# Light_s_Thrill.net
KiCad netlist of a schematic drawn in EAGLE
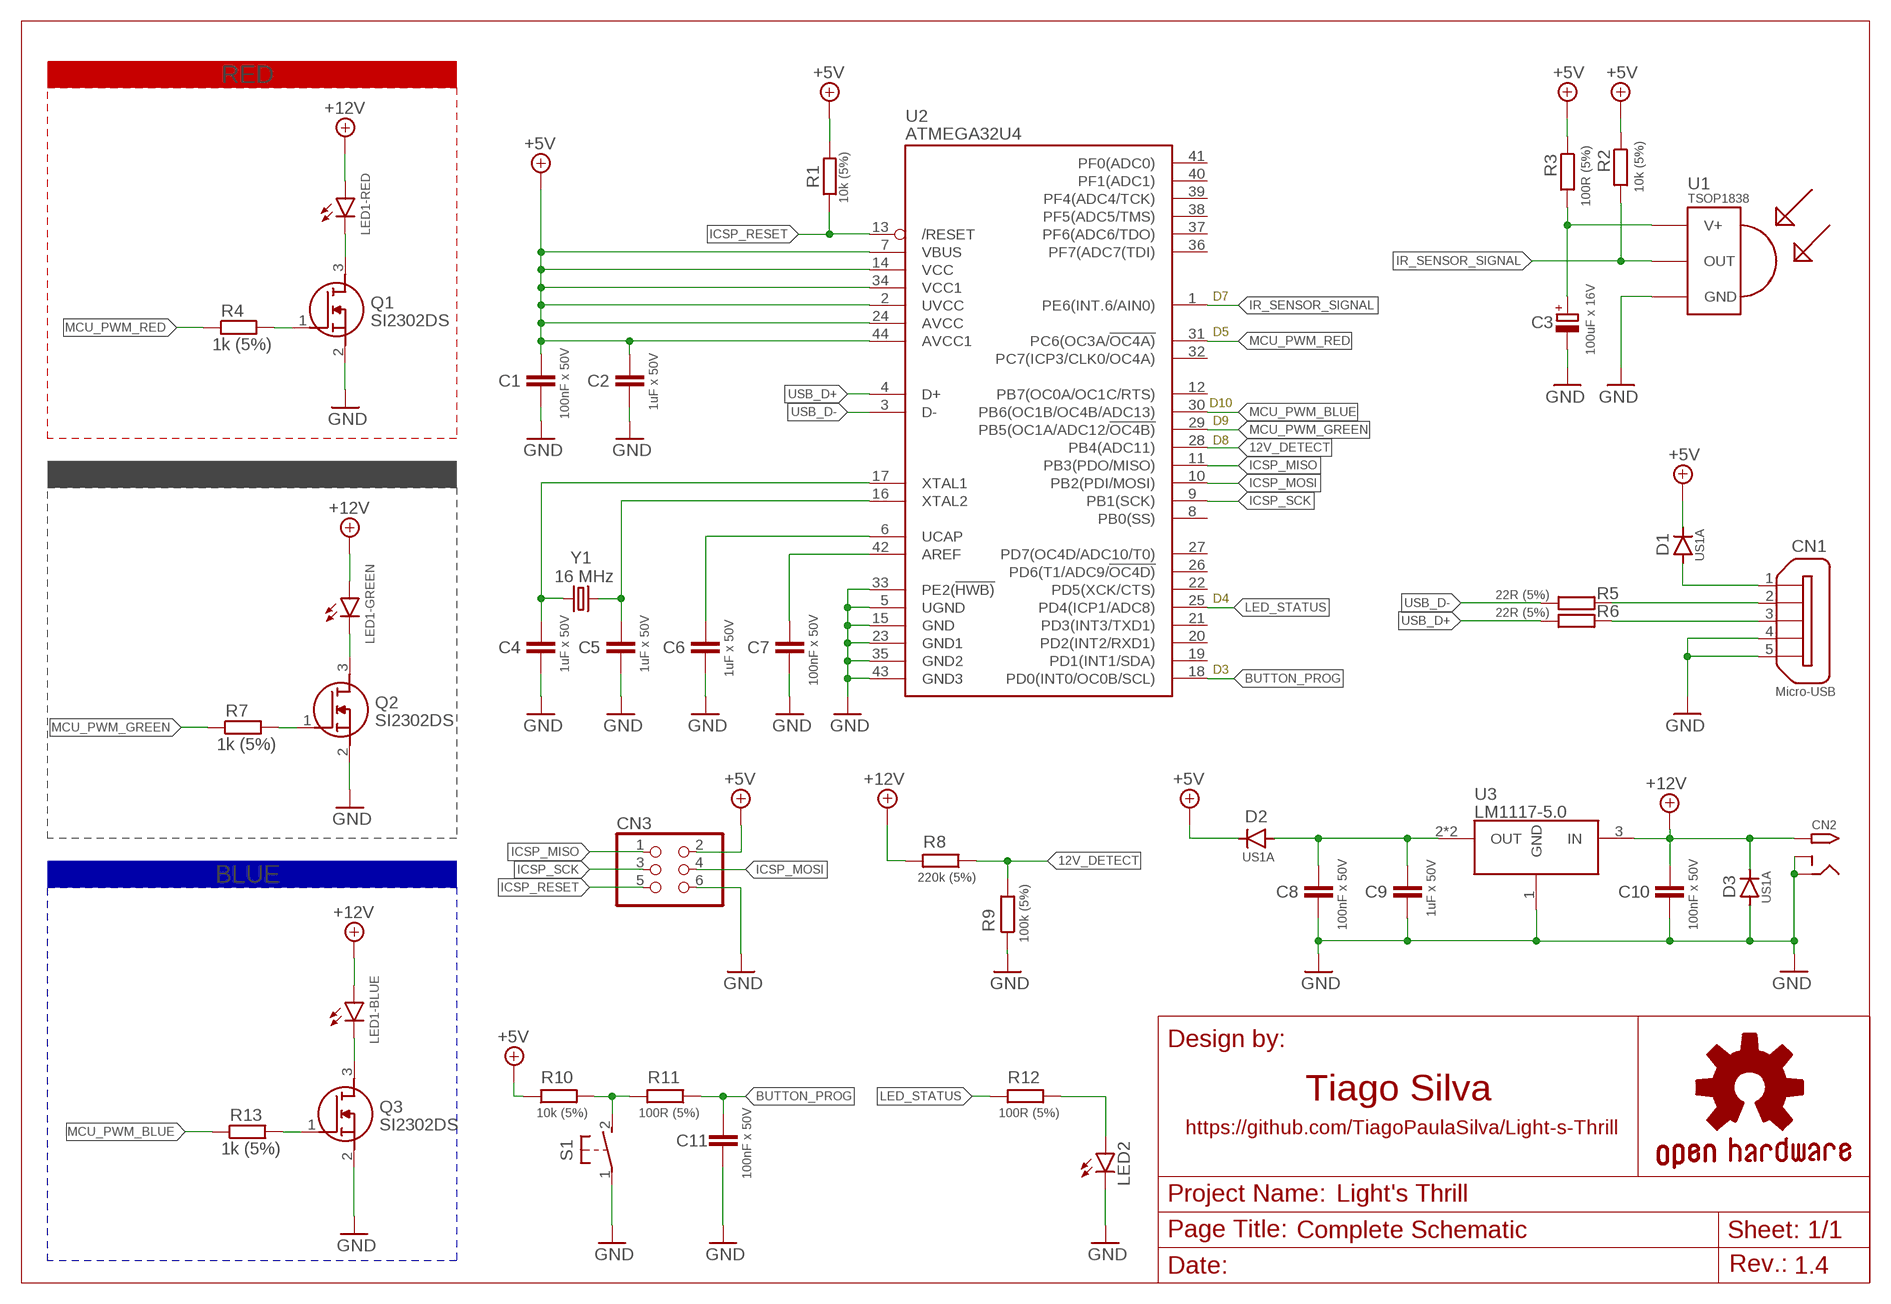
[diagram p0: schematic, sheet 1]

(export (version "E")
  (design (tool "Eeschema 10.0.6"))
  (components
    (comp (ref "C1")
      (value "100nF x 50V")
      (footprint "eagle-import:C0805")
      (libsource (lib "eagle-import") (part "C-EUC0805"))
    )
    (comp (ref "C2")
      (value "1uF x 50V")
      (footprint "eagle-import:C0805")
      (libsource (lib "eagle-import") (part "C-EUC0805"))
    )
    (comp (ref "C3")
      (value "100uF x 16V")
      (footprint "eagle-import:E2-5")
      (libsource (lib "eagle-import") (part "CPOL-EUE2-5"))
    )
    (comp (ref "C4")
      (value "1uF x 50V")
      (footprint "eagle-import:C0805")
      (libsource (lib "eagle-import") (part "C-EUC0805"))
    )
    (comp (ref "C5")
      (value "1uF x 50V")
      (footprint "eagle-import:C0805")
      (libsource (lib "eagle-import") (part "C-EUC0805"))
    )
    (comp (ref "C6")
      (value "1uF x 50V")
      (footprint "eagle-import:C0805")
      (libsource (lib "eagle-import") (part "C-EUC0805"))
    )
    (comp (ref "C7")
      (value "100nF x 50V")
      (footprint "eagle-import:C0805")
      (libsource (lib "eagle-import") (part "C-EUC0805"))
    )
    (comp (ref "C8")
      (value "100nF x 50V")
      (footprint "eagle-import:C0805")
      (libsource (lib "eagle-import") (part "C-EUC0805"))
    )
    (comp (ref "C9")
      (value "1uF x 50V")
      (footprint "eagle-import:C0805")
      (libsource (lib "eagle-import") (part "C-EUC0805"))
    )
    (comp (ref "C10")
      (value "100nF x 50V")
      (footprint "eagle-import:C0805")
      (libsource (lib "eagle-import") (part "C-EUC0805"))
    )
    (comp (ref "C11")
      (value "100nF x 50V")
      (footprint "eagle-import:C0805")
      (libsource (lib "eagle-import") (part "C-EUC0805"))
    )
    (comp (ref "CN1")
      (value "Micro-USB")
      (footprint "eagle-import:ZX62D-B-5PA8")
      (fields (field (name "MF") "Hirose") (field (name "MPN") "ZX62D-B-5PA8"))
      (libsource (lib "eagle-import") (part "ZX62D-B-5PA8"))
    )
    (comp (ref "CN2")
      (value "2.1MMJACKTHM")
      (footprint "eagle-import:PJ-102A")
      (libsource (lib "eagle-import") (part "2.1MMJACKTHM"))
    )
    (comp (ref "CN3")
      (value "2x3")
      (footprint "eagle-import:2X03")
      (libsource (lib "eagle-import") (part "PINHD-2X3"))
    )
    (comp (ref "D1")
      (value "US1A")
      (footprint "eagle-import:SOD-123_MINI-SMA")
      (libsource (lib "eagle-import") (part "CGRM400-G7"))
    )
    (comp (ref "D2")
      (value "US1A")
      (footprint "eagle-import:SOD-123_MINI-SMA")
      (libsource (lib "eagle-import") (part "CGRM400-G7"))
    )
    (comp (ref "D3")
      (value "US1A")
      (footprint "eagle-import:SOD-123_MINI-SMA")
      (libsource (lib "eagle-import") (part "CGRM400-G7"))
    )
    (comp (ref "LED1")
      (value "RGB_LED_STRIP")
      (footprint "eagle-import:STRIP-CONNECTOR")
      (libsource (lib "eagle-import") (part "RGB_LED_STRIP"))
    )
    (comp (ref "LED2")
      (value "Red")
      (footprint "eagle-import:CHIPLED_0805")
      (libsource (lib "eagle-import") (part "LEDCHIPLED_0805"))
    )
    (comp (ref "Q1")
      (value "SI2302DS")
      (footprint "eagle-import:SOT95P230X110-3N")
      (libsource (lib "eagle-import") (part "SI2302DS"))
    )
    (comp (ref "Q2")
      (value "SI2302DS")
      (footprint "eagle-import:SOT95P230X110-3N")
      (libsource (lib "eagle-import") (part "SI2302DS"))
    )
    (comp (ref "Q3")
      (value "SI2302DS")
      (footprint "eagle-import:SOT95P230X110-3N")
      (libsource (lib "eagle-import") (part "SI2302DS"))
    )
    (comp (ref "R1")
      (value "10k (5%)")
      (footprint "eagle-import:R0805")
      (libsource (lib "eagle-import") (part "R-EU_R0805"))
    )
    (comp (ref "R2")
      (value "10k (5%)")
      (footprint "eagle-import:R0805")
      (libsource (lib "eagle-import") (part "R-EU_R0805"))
    )
    (comp (ref "R3")
      (value "100R (5%)")
      (footprint "eagle-import:R0805")
      (libsource (lib "eagle-import") (part "R-EU_R0805"))
    )
    (comp (ref "R4")
      (value "1k (5%)")
      (footprint "eagle-import:R0805")
      (libsource (lib "eagle-import") (part "R-EU_R0805"))
    )
    (comp (ref "R5")
      (value "22R (5%)")
      (footprint "eagle-import:R0805")
      (libsource (lib "eagle-import") (part "R-EU_R0805"))
    )
    (comp (ref "R6")
      (value "22R (5%)")
      (footprint "eagle-import:R0805")
      (libsource (lib "eagle-import") (part "R-EU_R0805"))
    )
    (comp (ref "R7")
      (value "1k (5%)")
      (footprint "eagle-import:R0805")
      (libsource (lib "eagle-import") (part "R-EU_R0805"))
    )
    (comp (ref "R8")
      (value "220k (5%)")
      (footprint "eagle-import:R0805")
      (libsource (lib "eagle-import") (part "R-EU_R0805"))
    )
    (comp (ref "R9")
      (value "100k (5%)")
      (footprint "eagle-import:R0805")
      (libsource (lib "eagle-import") (part "R-EU_R0805"))
    )
    (comp (ref "R10")
      (value "10k (5%)")
      (footprint "eagle-import:R0805")
      (libsource (lib "eagle-import") (part "R-EU_R0805"))
    )
    (comp (ref "R11")
      (value "100R (5%)")
      (footprint "eagle-import:R0805")
      (libsource (lib "eagle-import") (part "R-EU_R0805"))
    )
    (comp (ref "R12")
      (value "100R (5%)")
      (footprint "eagle-import:R0805")
      (libsource (lib "eagle-import") (part "R-EU_R0805"))
    )
    (comp (ref "R13")
      (value "1k (5%)")
      (footprint "eagle-import:R0805")
      (libsource (lib "eagle-import") (part "R-EU_R0805"))
    )
    (comp (ref "S1")
      (value "DTSM-3")
      (footprint "eagle-import:DTSM-3")
      (libsource (lib "eagle-import") (part "DTSM-3"))
    )
    (comp (ref "U1")
      (value "TSOP1838")
      (footprint "eagle-import:TSOP18XX")
      (fields (field (name "MF") "Vishay"))
      (libsource (lib "eagle-import") (part "TSOP1838"))
    )
    (comp (ref "U2")
      (value "ATMEGA32U4")
      (footprint "eagle-import:TQFP44")
      (libsource (lib "eagle-import") (part "ATMEGA32U4-AU"))
    )
    (comp (ref "U3")
      (value "LM1117-5.0")
      (footprint "eagle-import:SOT223")
      (fields (field (name "MF") "Texas Instruments") (field (name "MP") "LM1117IMP50"))
      (libsource (lib "eagle-import") (part "LM1117IMP-5.0-NOPB"))
    )
    (comp (ref "Y1")
      (value "16 MHz")
      (footprint "eagle-import:5.0X3.2_KX-9A")
      (libsource (lib "eagle-import") (part "KX-9A"))
    )
  )
  (nets
    (net (code "1") (name "+5V") (class "Default")
      (node (ref "C1") (pin "1") (pinfunction "1_1") (pintype "passive"))
      (node (ref "C2") (pin "1") (pinfunction "1_1") (pintype "passive"))
      (node (ref "CN3") (pin "2") (pinfunction "2_2") (pintype "passive"))
      (node (ref "D1") (pin "C") (pinfunction "C_C") (pintype "passive"))
      (node (ref "D2") (pin "C") (pinfunction "C_C") (pintype "passive"))
      (node (ref "R1") (pin "2") (pinfunction "2_2") (pintype "passive"))
      (node (ref "R10") (pin "1") (pinfunction "1_1") (pintype "passive"))
      (node (ref "R2") (pin "1") (pinfunction "1_1") (pintype "passive"))
      (node (ref "R3") (pin "1") (pinfunction "1_1") (pintype "passive"))
      (node (ref "U2") (pin "14") (pinfunction "VCC_14") (pintype "bidirectional"))
      (node (ref "U2") (pin "2") (pinfunction "UVCC_2") (pintype "bidirectional"))
      (node (ref "U2") (pin "24") (pinfunction "AVCC_24") (pintype "bidirectional"))
      (node (ref "U2") (pin "34") (pinfunction "VCC1_34") (pintype "bidirectional"))
      (node (ref "U2") (pin "44") (pinfunction "AVCC1_44") (pintype "bidirectional"))
      (node (ref "U2") (pin "7") (pinfunction "VBUS_7") (pintype "bidirectional"))
    )
    (net (code "2") (name "+12V") (class "Default")
      (node (ref "C10") (pin "1") (pinfunction "1_1") (pintype "passive"))
      (node (ref "CN2") (pin "TIP") (pinfunction "TIP_TIP") (pintype "bidirectional"))
      (node (ref "D3") (pin "C") (pinfunction "C_C") (pintype "passive"))
      (node (ref "LED1") (pin "1") (pinfunction "ANODE_1") (pintype "bidirectional"))
      (node (ref "R8") (pin "2") (pinfunction "2_2") (pintype "passive"))
      (node (ref "U3") (pin "3") (pinfunction "IN_3") (pintype "input"))
    )
    (net (code "3") (name "12V_DETECT") (class "Default")
      (node (ref "R8") (pin "1") (pinfunction "1_1") (pintype "passive"))
      (node (ref "R9") (pin "2") (pinfunction "2_2") (pintype "passive"))
      (node (ref "U2") (pin "28") (pinfunction "PB4(ADC11)_28") (pintype "bidirectional"))
    )
    (net (code "4") (name "BUTTON_PROG") (class "Default")
      (node (ref "C11") (pin "1") (pinfunction "1_1") (pintype "passive"))
      (node (ref "R11") (pin "1") (pinfunction "1_1") (pintype "passive"))
      (node (ref "U2") (pin "18") (pinfunction "PD0(INT0/OC0B/SCL)_18") (pintype "bidirectional"))
    )
    (net (code "5") (name "GND") (class "Default")
      (node (ref "C1") (pin "2") (pinfunction "2_2") (pintype "passive"))
      (node (ref "C10") (pin "2") (pinfunction "2_2") (pintype "passive"))
      (node (ref "C11") (pin "2") (pinfunction "2_2") (pintype "passive"))
      (node (ref "C2") (pin "2") (pinfunction "2_2") (pintype "passive"))
      (node (ref "C3") (pin "-") (pinfunction "-_-") (pintype "passive"))
      (node (ref "C4") (pin "2") (pinfunction "2_2") (pintype "passive"))
      (node (ref "C5") (pin "2") (pinfunction "2_2") (pintype "passive"))
      (node (ref "C6") (pin "2") (pinfunction "2_2") (pintype "passive"))
      (node (ref "C7") (pin "2") (pinfunction "2_2") (pintype "passive"))
      (node (ref "C8") (pin "2") (pinfunction "2_2") (pintype "passive"))
      (node (ref "C9") (pin "2") (pinfunction "2_2") (pintype "passive"))
      (node (ref "CN1") (pin "4") (pinfunction "4_4") (pintype "passive"))
      (node (ref "CN1") (pin "5") (pinfunction "5_5") (pintype "passive"))
      (node (ref "CN2") (pin "RING") (pinfunction "RING_RING") (pintype "bidirectional"))
      (node (ref "CN2") (pin "RING_SW") (pinfunction "RING_SW_RING_SW") (pintype "bidirectional"))
      (node (ref "CN3") (pin "6") (pinfunction "6_6") (pintype "passive"))
      (node (ref "D3") (pin "A") (pinfunction "A_A") (pintype "passive"))
      (node (ref "LED2") (pin "C") (pinfunction "C_C") (pintype "passive"))
      (node (ref "Q1") (pin "2") (pinfunction "S_2") (pintype "bidirectional"))
      (node (ref "Q2") (pin "2") (pinfunction "S_2") (pintype "bidirectional"))
      (node (ref "Q3") (pin "2") (pinfunction "S_2") (pintype "bidirectional"))
      (node (ref "R9") (pin "1") (pinfunction "1_1") (pintype "passive"))
      (node (ref "S1") (pin "1") (pinfunction "1_1") (pintype "passive"))
      (node (ref "U1") (pin "GND") (pinfunction "GND_GND") (pintype "bidirectional"))
      (node (ref "U2") (pin "15") (pinfunction "GND_15") (pintype "bidirectional"))
      (node (ref "U2") (pin "23") (pinfunction "GND1_23") (pintype "bidirectional"))
      (node (ref "U2") (pin "33") (pinfunction "PE2(~{HWB})_33") (pintype "bidirectional"))
      (node (ref "U2") (pin "35") (pinfunction "GND2_35") (pintype "bidirectional"))
      (node (ref "U2") (pin "43") (pinfunction "GND3_43") (pintype "bidirectional"))
      (node (ref "U2") (pin "5") (pinfunction "UGND_5") (pintype "bidirectional"))
      (node (ref "U3") (pin "1") (pinfunction "GND_1") (pintype "passive"))
    )
    (net (code "6") (name "ICSP_MISO") (class "Default")
      (node (ref "CN3") (pin "1") (pinfunction "1_1") (pintype "passive"))
      (node (ref "U2") (pin "11") (pinfunction "PB3(PDO/MISO)_11") (pintype "bidirectional"))
    )
    (net (code "7") (name "ICSP_MOSI") (class "Default")
      (node (ref "CN3") (pin "4") (pinfunction "4_4") (pintype "passive"))
      (node (ref "U2") (pin "10") (pinfunction "PB2(PDI/MOSI)_10") (pintype "bidirectional"))
    )
    (net (code "8") (name "ICSP_RESET") (class "Default")
      (node (ref "CN3") (pin "5") (pinfunction "5_5") (pintype "passive"))
      (node (ref "R1") (pin "1") (pinfunction "1_1") (pintype "passive"))
      (node (ref "U2") (pin "13") (pinfunction "/RESET_13") (pintype "bidirectional"))
    )
    (net (code "9") (name "ICSP_SCK") (class "Default")
      (node (ref "CN3") (pin "3") (pinfunction "3_3") (pintype "passive"))
      (node (ref "U2") (pin "9") (pinfunction "PB1(SCK)_9") (pintype "bidirectional"))
    )
    (net (code "10") (name "IR_SENSOR_SIGNAL") (class "Default")
      (node (ref "R2") (pin "2") (pinfunction "2_2") (pintype "passive"))
      (node (ref "U1") (pin "OUT") (pinfunction "OUT_OUT") (pintype "bidirectional"))
      (node (ref "U2") (pin "1") (pinfunction "PE6(INT.6/AIN0)_1") (pintype "bidirectional"))
    )
    (net (code "11") (name "LED_STATUS") (class "Default")
      (node (ref "R12") (pin "1") (pinfunction "1_1") (pintype "passive"))
      (node (ref "U2") (pin "25") (pinfunction "PD4(ICP1/ADC8)_25") (pintype "bidirectional"))
    )
    (net (code "12") (name "MCU_PWM_BLUE") (class "Default")
      (node (ref "R13") (pin "1") (pinfunction "1_1") (pintype "passive"))
      (node (ref "U2") (pin "30") (pinfunction "PB6(OC1B/OC4B/ADC13)_30") (pintype "bidirectional"))
    )
    (net (code "13") (name "MCU_PWM_GREEN") (class "Default")
      (node (ref "R7") (pin "1") (pinfunction "1_1") (pintype "passive"))
      (node (ref "U2") (pin "29") (pinfunction "PB5(OC1A/ADC12/~{OC4B})_29") (pintype "bidirectional"))
    )
    (net (code "14") (name "MCU_PWM_RED") (class "Default")
      (node (ref "R4") (pin "1") (pinfunction "1_1") (pintype "passive"))
      (node (ref "U2") (pin "31") (pinfunction "PC6(OC3A/~{OC4A})_31") (pintype "bidirectional"))
    )
    (net (code "15") (name "Net-(C8-Pad1)") (class "Default")
      (node (ref "C8") (pin "1") (pinfunction "1_1") (pintype "passive"))
      (node (ref "C9") (pin "1") (pinfunction "1_1") (pintype "passive"))
      (node (ref "D2") (pin "A") (pinfunction "A_A") (pintype "passive"))
      (node (ref "U3") (pin "2") (pinfunction "OUT_2") (pintype "output"))
      (node (ref "U3") (pin "4") (pinfunction "OUT_4") (pintype "output"))
    )
    (net (code "16") (name "Net-(CN1-Pad1)") (class "Default")
      (node (ref "CN1") (pin "1") (pinfunction "1_1") (pintype "passive"))
      (node (ref "D1") (pin "A") (pinfunction "A_A") (pintype "passive"))
    )
    (net (code "17") (name "Net-(CN1-Pad2)") (class "Default")
      (node (ref "CN1") (pin "2") (pinfunction "2_2") (pintype "passive"))
      (node (ref "R5") (pin "2") (pinfunction "2_2") (pintype "passive"))
    )
    (net (code "18") (name "Net-(CN1-Pad3)") (class "Default")
      (node (ref "CN1") (pin "3") (pinfunction "3_3") (pintype "passive"))
      (node (ref "R6") (pin "2") (pinfunction "2_2") (pintype "passive"))
    )
    (net (code "19") (name "Net-(LED1A-C)") (class "Default")
      (node (ref "LED1") (pin "4") (pinfunction "C_4") (pintype "passive"))
      (node (ref "Q3") (pin "3") (pinfunction "D_3") (pintype "bidirectional"))
    )
    (net (code "20") (name "Net-(LED1B-C)") (class "Default")
      (node (ref "LED1") (pin "2") (pinfunction "C_2") (pintype "passive"))
      (node (ref "Q2") (pin "3") (pinfunction "D_3") (pintype "bidirectional"))
    )
    (net (code "21") (name "Net-(LED1C-C)") (class "Default")
      (node (ref "LED1") (pin "3") (pinfunction "C_3") (pintype "passive"))
      (node (ref "Q1") (pin "3") (pinfunction "D_3") (pintype "bidirectional"))
    )
    (net (code "22") (name "Net-(LED2-PadA)") (class "Default")
      (node (ref "LED2") (pin "A") (pinfunction "A_A") (pintype "passive"))
      (node (ref "R12") (pin "2") (pinfunction "2_2") (pintype "passive"))
    )
    (net (code "23") (name "Net-(Q1-G)") (class "Default")
      (node (ref "Q1") (pin "1") (pinfunction "G_1") (pintype "bidirectional"))
      (node (ref "R4") (pin "2") (pinfunction "2_2") (pintype "passive"))
    )
    (net (code "24") (name "Net-(Q2-G)") (class "Default")
      (node (ref "Q2") (pin "1") (pinfunction "G_1") (pintype "bidirectional"))
      (node (ref "R7") (pin "2") (pinfunction "2_2") (pintype "passive"))
    )
    (net (code "25") (name "Net-(Q3-G)") (class "Default")
      (node (ref "Q3") (pin "1") (pinfunction "G_1") (pintype "bidirectional"))
      (node (ref "R13") (pin "2") (pinfunction "2_2") (pintype "passive"))
    )
    (net (code "26") (name "Net-(R10-Pad2)") (class "Default")
      (node (ref "R10") (pin "2") (pinfunction "2_2") (pintype "passive"))
      (node (ref "R11") (pin "2") (pinfunction "2_2") (pintype "passive"))
      (node (ref "S1") (pin "2") (pinfunction "2_2") (pintype "passive"))
    )
    (net (code "27") (name "Net-(U1-V+)") (class "Default")
      (node (ref "C3") (pin "+") (pinfunction "+_+") (pintype "passive"))
      (node (ref "R3") (pin "2") (pinfunction "2_2") (pintype "passive"))
      (node (ref "U1") (pin "VCC") (pinfunction "V+_VCC") (pintype "bidirectional"))
    )
    (net (code "28") (name "Net-(U2-AREF)") (class "Default")
      (node (ref "C7") (pin "1") (pinfunction "1_1") (pintype "passive"))
      (node (ref "U2") (pin "42") (pinfunction "AREF_42") (pintype "bidirectional"))
    )
    (net (code "29") (name "Net-(U2-UCAP)") (class "Default")
      (node (ref "C6") (pin "1") (pinfunction "1_1") (pintype "passive"))
      (node (ref "U2") (pin "6") (pinfunction "UCAP_6") (pintype "bidirectional"))
    )
    (net (code "30") (name "Net-(U2-XTAL1)") (class "Default")
      (node (ref "C4") (pin "1") (pinfunction "1_1") (pintype "passive"))
      (node (ref "U2") (pin "17") (pinfunction "XTAL1_17") (pintype "bidirectional"))
      (node (ref "Y1") (pin "1") (pinfunction "1_1") (pintype "passive"))
    )
    (net (code "31") (name "Net-(U2-XTAL2)") (class "Default")
      (node (ref "C5") (pin "1") (pinfunction "1_1") (pintype "passive"))
      (node (ref "U2") (pin "16") (pinfunction "XTAL2_16") (pintype "bidirectional"))
      (node (ref "Y1") (pin "3") (pinfunction "2_3") (pintype "passive"))
    )
    (net (code "32") (name "USB_D+") (class "Default")
      (node (ref "R6") (pin "1") (pinfunction "1_1") (pintype "passive"))
      (node (ref "U2") (pin "4") (pinfunction "D+_4") (pintype "bidirectional"))
    )
    (net (code "33") (name "USB_D-") (class "Default")
      (node (ref "R5") (pin "1") (pinfunction "1_1") (pintype "passive"))
      (node (ref "U2") (pin "3") (pinfunction "D-_3") (pintype "bidirectional"))
    )
    (net (code "34") (name "unconnected-(U2-PB0(SS)-Pad8)") (class "Default")
      (node (ref "U2") (pin "8") (pinfunction "PB0(SS)_8") (pintype "bidirectional"))
    )
    (net (code "35") (name "unconnected-(U2-PB7(OC0A{slash}OC1C{slash}RTS)-Pad12)") (class "Default")
      (node (ref "U2") (pin "12") (pinfunction "PB7(OC0A/OC1C/RTS)_12") (pintype "bidirectional"))
    )
    (net (code "36") (name "unconnected-(U2-PC7(ICP3{slash}CLK0{slash}OC4A)-Pad32)") (class "Default")
      (node (ref "U2") (pin "32") (pinfunction "PC7(ICP3/CLK0/OC4A)_32") (pintype "bidirectional"))
    )
    (net (code "37") (name "unconnected-(U2-PD1(INT1{slash}SDA)-Pad19)") (class "Default")
      (node (ref "U2") (pin "19") (pinfunction "PD1(INT1/SDA)_19") (pintype "bidirectional"))
    )
    (net (code "38") (name "unconnected-(U2-PD2(INT2{slash}RXD1)-Pad20)") (class "Default")
      (node (ref "U2") (pin "20") (pinfunction "PD2(INT2/RXD1)_20") (pintype "bidirectional"))
    )
    (net (code "39") (name "unconnected-(U2-PD3(INT3{slash}TXD1)-Pad21)") (class "Default")
      (node (ref "U2") (pin "21") (pinfunction "PD3(INT3/TXD1)_21") (pintype "bidirectional"))
    )
    (net (code "40") (name "unconnected-(U2-PD5(XCK{slash}CTS)-Pad22)") (class "Default")
      (node (ref "U2") (pin "22") (pinfunction "PD5(XCK/CTS)_22") (pintype "bidirectional"))
    )
    (net (code "41") (name "unconnected-(U2-PD6(T1{slash}ADC9{slash}~{OC4D})-Pad26)") (class "Default")
      (node (ref "U2") (pin "26") (pinfunction "PD6(T1/ADC9/~{OC4D})_26") (pintype "bidirectional"))
    )
    (net (code "42") (name "unconnected-(U2-PD7(OC4D{slash}ADC10{slash}T0)-Pad27)") (class "Default")
      (node (ref "U2") (pin "27") (pinfunction "PD7(OC4D/ADC10/T0)_27") (pintype "bidirectional"))
    )
    (net (code "43") (name "unconnected-(U2-PF0(ADC0)-Pad41)") (class "Default")
      (node (ref "U2") (pin "41") (pinfunction "PF0(ADC0)_41") (pintype "bidirectional"))
    )
    (net (code "44") (name "unconnected-(U2-PF1(ADC1)-Pad40)") (class "Default")
      (node (ref "U2") (pin "40") (pinfunction "PF1(ADC1)_40") (pintype "bidirectional"))
    )
    (net (code "45") (name "unconnected-(U2-PF4(ADC4{slash}TCK)-Pad39)") (class "Default")
      (node (ref "U2") (pin "39") (pinfunction "PF4(ADC4/TCK)_39") (pintype "bidirectional"))
    )
    (net (code "46") (name "unconnected-(U2-PF5(ADC5{slash}TMS)-Pad38)") (class "Default")
      (node (ref "U2") (pin "38") (pinfunction "PF5(ADC5/TMS)_38") (pintype "bidirectional"))
    )
    (net (code "47") (name "unconnected-(U2-PF6(ADC6{slash}TDO)-Pad37)") (class "Default")
      (node (ref "U2") (pin "37") (pinfunction "PF6(ADC6/TDO)_37") (pintype "bidirectional"))
    )
    (net (code "48") (name "unconnected-(U2-PF7(ADC7(TDI)-Pad36)") (class "Default")
      (node (ref "U2") (pin "36") (pinfunction "PF7(ADC7(TDI)_36") (pintype "bidirectional"))
    )
  )
)
